# Power.net
KiCad netlist of a schematic drawn in Altium Designer
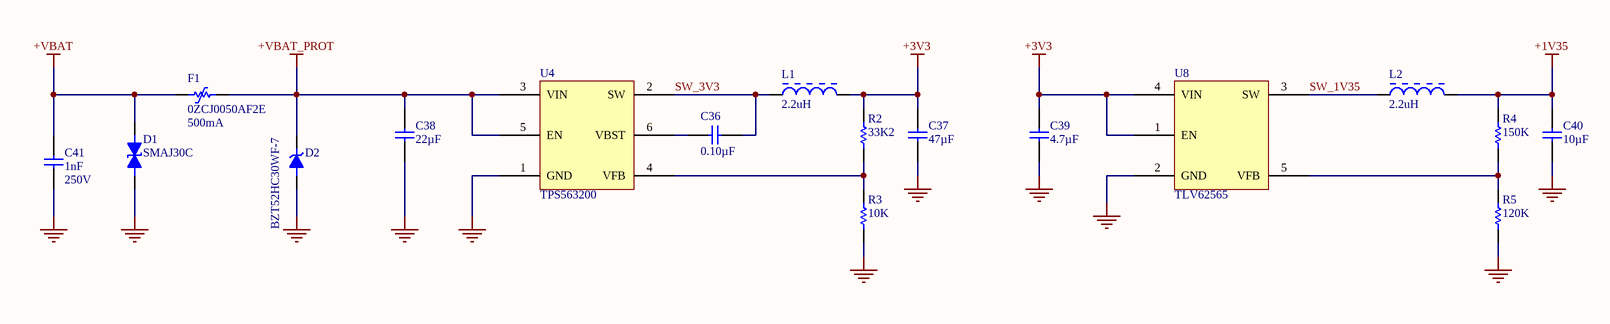
[diagram p0: Power.SchDoc]

(export (version "E")
  (design (tool "Eeschema 10.0.6"))
  (components
    (comp (ref "C36")
      (value "0.10µF")
      (footprint "CAP-0402-M")
      (fields
        (field (name "PART NUMBER") "CC0402KRX7R8BB104")
        (field (name "TOLERANCE") "±10%")
        (field (name "VOLTAGE") "25V")
      )
      (libsource (lib "Capacitors") (part "Capacitor"))
    )
    (comp (ref "C37")
      (value "47µF")
      (footprint "CAP-1210-M")
      (fields
        (field (name "PART NUMBER") "CC1210MKX5R5BB476")
        (field (name "TOLERANCE") "±20%")
        (field (name "VOLTAGE") "6.3V")
      )
      (libsource (lib "Capacitors") (part "Capacitor"))
    )
    (comp (ref "C38")
      (value "22µF")
      (footprint "CAP-1210-M")
      (fields
        (field (name "PART NUMBER") "CC1210KKX5R8BB226")
        (field (name "TOLERANCE") "±10%")
        (field (name "VOLTAGE") "25V")
      )
      (libsource (lib "Capacitors") (part "Capacitor"))
    )
    (comp (ref "C39")
      (value "4.7µF")
      (footprint "CAP-0805-M")
      (fields
        (field (name "PART NUMBER") "CC0805KKX5R5BB475")
        (field (name "TOLERANCE") "±10%")
        (field (name "VOLTAGE") "6.3V")
      )
      (libsource (lib "Capacitors") (part "Capacitor"))
    )
    (comp (ref "C40")
      (value "10µF")
      (footprint "CAP-0805-M")
      (fields
        (field (name "PART NUMBER") "CC0805KKX5R5BB106")
        (field (name "TOLERANCE") "±10%")
        (field (name "VOLTAGE") "6.3V")
      )
      (libsource (lib "Capacitors") (part "Capacitor"))
    )
    (comp (ref "C41")
      (value "1nF")
      (footprint "CAP-0805-M")
      (fields
        (field (name "PART NUMBER") "CC0805KRX7RYBB102")
        (field (name "TOLERANCE") "±10%")
        (field (name "VOLTAGE") "250V")
        (field (name "MANUFACTURER") "Yageo")
      )
      (libsource (lib "Capacitors") (part "Capacitor"))
    )
    (comp (ref "D1")
      (value "SMAJ30C")
      (footprint "SON127P500X135-2N")
      (libsource (lib "Hub-UV17") (part "SMAJ30C"))
    )
    (comp (ref "D2")
      (value "BZT52HC30WF-7")
      (footprint "SODFL340X115-2N")
      (libsource (lib "Hub-UV17") (part "BZT52HC30WF-7"))
    )
    (comp (ref "F1")
      (value "0ZCJ0050AF2E")
      (footprint "0ZCJ-1206-0.9")
      (fields (field (name "ALTIUM_VALUE") "500mA"))
      (libsource (lib "Hub-UV17") (part "0ZCJ0050AF2E"))
    )
    (comp (ref "L1")
      (value "2.2uH")
      (footprint "INDP8080X40N")
      (fields (field (name "Comment") "SRN8040-2R2Y"))
      (libsource (lib "Hub-UV17") (part "SRN8040-2R2Y"))
    )
    (comp (ref "L2")
      (value "2.2uH")
      (footprint "INDP4848X28N")
      (fields (field (name "Comment") "SRR4028-2R2Y"))
      (libsource (lib "Hub-UV17") (part "SRR4028-2R2Y"))
    )
    (comp (ref "R2")
      (value "33K2")
      (footprint "RES-0603-M")
      (fields
        (field (name "PART NUMBER") "RC0603FR-0733K2L")
        (field (name "TOLERANCE") "1%")
        (field (name "POWER") "1/10 W")
      )
      (libsource (lib "Resistors") (part "Resistor"))
    )
    (comp (ref "R3")
      (value "10K")
      (footprint "RES-0603-M")
      (fields
        (field (name "PART NUMBER") "RC0603FR-0710KL")
        (field (name "TOLERANCE") "1%")
        (field (name "POWER") "1/10 W")
      )
      (libsource (lib "Resistors") (part "Resistor"))
    )
    (comp (ref "R4")
      (value "150K")
      (footprint "RES-0603-M")
      (fields
        (field (name "PART NUMBER") "RC0603FR-07150KL")
        (field (name "TOLERANCE") "1%")
        (field (name "POWER") "1/10 W")
      )
      (libsource (lib "Resistors") (part "Resistor"))
    )
    (comp (ref "R5")
      (value "120K")
      (footprint "RES-0603-M")
      (fields
        (field (name "PART NUMBER") "RC0603FR-07120KL")
        (field (name "TOLERANCE") "1%")
        (field (name "POWER") "1/10 W")
      )
      (libsource (lib "Resistors") (part "Resistor"))
    )
    (comp (ref "U4")
      (value "TPS563200")
      (footprint "TSOP95P280X110-6N")
      (description "4.5-V To 17-V Input, 2-A, 3-A Synchronous Step-Down Voltage Regulator In  6 Pin SOT-23")
      (libsource (lib "Hub-UV17") (part "TPS563200"))
    )
    (comp (ref "U8")
      (value "TLV62565")
      (footprint "SOT95P280X145-5N")
      (description "x 1.5-A High Efficiency Step-Down Converters in SOT-23 5-Pin Package")
      (libsource (lib "Hub-UV17") (part "TLV62565"))
    )
  )
  (nets
    (net (code "1") (name "+1V35") (class "Default")
      (node (ref "C40") (pin "2") (pinfunction "2_2") (pintype "passive"))
      (node (ref "L2") (pin "2") (pinfunction "2_2") (pintype "passive"))
      (node (ref "R4") (pin "2") (pinfunction "2_2") (pintype "passive"))
    )
    (net (code "2") (name "+3V3") (class "Default")
      (node (ref "C37") (pin "2") (pinfunction "2_2") (pintype "passive"))
      (node (ref "C39") (pin "2") (pinfunction "2_2") (pintype "passive"))
      (node (ref "L1") (pin "2") (pinfunction "2_2") (pintype "passive"))
      (node (ref "R2") (pin "2") (pinfunction "2_2") (pintype "passive"))
      (node (ref "U8") (pin "1") (pinfunction "EN_1") (pintype "passive"))
      (node (ref "U8") (pin "4") (pinfunction "VIN_4") (pintype "power_in"))
    )
    (net (code "3") (name "+VBAT") (class "Default")
      (node (ref "C41") (pin "1") (pinfunction "1_1") (pintype "passive"))
      (node (ref "D1") (pin "1") (pinfunction "1_1") (pintype "passive"))
      (node (ref "F1") (pin "1") (pinfunction "1_1") (pintype "passive"))
    )
    (net (code "4") (name "+VBAT_PROT") (class "Default")
      (node (ref "C38") (pin "2") (pinfunction "2_2") (pintype "passive"))
      (node (ref "D2") (pin "1") (pinfunction "K_1") (pintype "passive"))
      (node (ref "F1") (pin "2") (pinfunction "2_2") (pintype "passive"))
      (node (ref "U4") (pin "3") (pinfunction "VIN_3") (pintype "power_in"))
      (node (ref "U4") (pin "5") (pinfunction "EN_5") (pintype "passive"))
    )
    (net (code "5") (name "/SW_1V35") (class "Default")
      (node (ref "L2") (pin "1") (pinfunction "1_1") (pintype "passive"))
      (node (ref "U8") (pin "3") (pinfunction "SW_3") (pintype "passive"))
    )
    (net (code "6") (name "/SW_3V3") (class "Default")
      (node (ref "C36") (pin "2") (pinfunction "2_2") (pintype "passive"))
      (node (ref "L1") (pin "1") (pinfunction "1_1") (pintype "passive"))
      (node (ref "U4") (pin "2") (pinfunction "SW_2") (pintype "passive"))
    )
    (net (code "7") (name "GND") (class "Default")
      (node (ref "C37") (pin "1") (pinfunction "1_1") (pintype "passive"))
      (node (ref "C38") (pin "1") (pinfunction "1_1") (pintype "passive"))
      (node (ref "C39") (pin "1") (pinfunction "1_1") (pintype "passive"))
      (node (ref "C40") (pin "1") (pinfunction "1_1") (pintype "passive"))
      (node (ref "C41") (pin "2") (pinfunction "2_2") (pintype "passive"))
      (node (ref "D1") (pin "2") (pinfunction "2_2") (pintype "passive"))
      (node (ref "D2") (pin "2") (pinfunction "A_2") (pintype "passive"))
      (node (ref "R3") (pin "1") (pinfunction "1_1") (pintype "passive"))
      (node (ref "R5") (pin "1") (pinfunction "1_1") (pintype "passive"))
      (node (ref "U4") (pin "1") (pinfunction "GND_1") (pintype "passive"))
      (node (ref "U8") (pin "2") (pinfunction "GND_2") (pintype "passive"))
    )
    (net (code "8") (name "Net-(U4-VBST)") (class "Default")
      (node (ref "C36") (pin "1") (pinfunction "1_1") (pintype "passive"))
      (node (ref "U4") (pin "6") (pinfunction "VBST_6") (pintype "passive"))
    )
    (net (code "9") (name "Net-(U4-VFB)") (class "Default")
      (node (ref "R2") (pin "1") (pinfunction "1_1") (pintype "passive"))
      (node (ref "R3") (pin "2") (pinfunction "2_2") (pintype "passive"))
      (node (ref "U4") (pin "4") (pinfunction "VFB_4") (pintype "passive"))
    )
    (net (code "10") (name "Net-(U8-VFB)") (class "Default")
      (node (ref "R4") (pin "1") (pinfunction "1_1") (pintype "passive"))
      (node (ref "R5") (pin "2") (pinfunction "2_2") (pintype "passive"))
      (node (ref "U8") (pin "5") (pinfunction "VFB_5") (pintype "passive"))
    )
  )
)
